# USB.net
KiCad netlist of a schematic drawn in Altium Designer
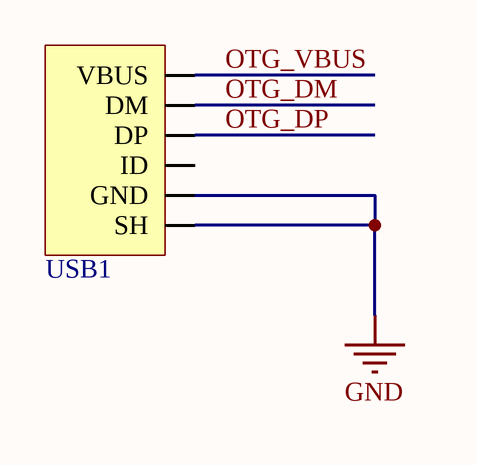
[diagram p0: USB.SchDoc]

(export (version "E")
  (design (tool "Eeschema 10.0.6"))
  (components
    (comp (ref "USB1")
      (value "USB_Micro")
      (footprint "PCB_USB:USB_Micro-AB")
      (description "USB")
      (libsource (lib "SCH_USB") (part "USB_Micro"))
    )
  )
  (nets
    (net (code "1") (name "/OTG_DM") (class "Default")
      (node (ref "USB1") (pin "2") (pinfunction "DM_2") (pintype "passive"))
    )
    (net (code "2") (name "/OTG_DP") (class "Default")
      (node (ref "USB1") (pin "3") (pinfunction "DP_3") (pintype "passive"))
    )
    (net (code "3") (name "/OTG_VBUS") (class "Default")
      (node (ref "USB1") (pin "1") (pinfunction "VBUS_1") (pintype "passive"))
    )
    (net (code "4") (name "GND") (class "Default")
      (node (ref "USB1") (pin "0") (pinfunction "SH_0") (pintype "passive"))
      (node (ref "USB1") (pin "5") (pinfunction "GND_5") (pintype "passive"))
    )
    (net (code "5") (name "unconnected-(USB1-ID-Pad4)") (class "Default")
      (node (ref "USB1") (pin "4") (pinfunction "ID_4") (pintype "passive"))
    )
  )
)
